# 08_-_USB.net
KiCad netlist of a schematic drawn in Altium Designer
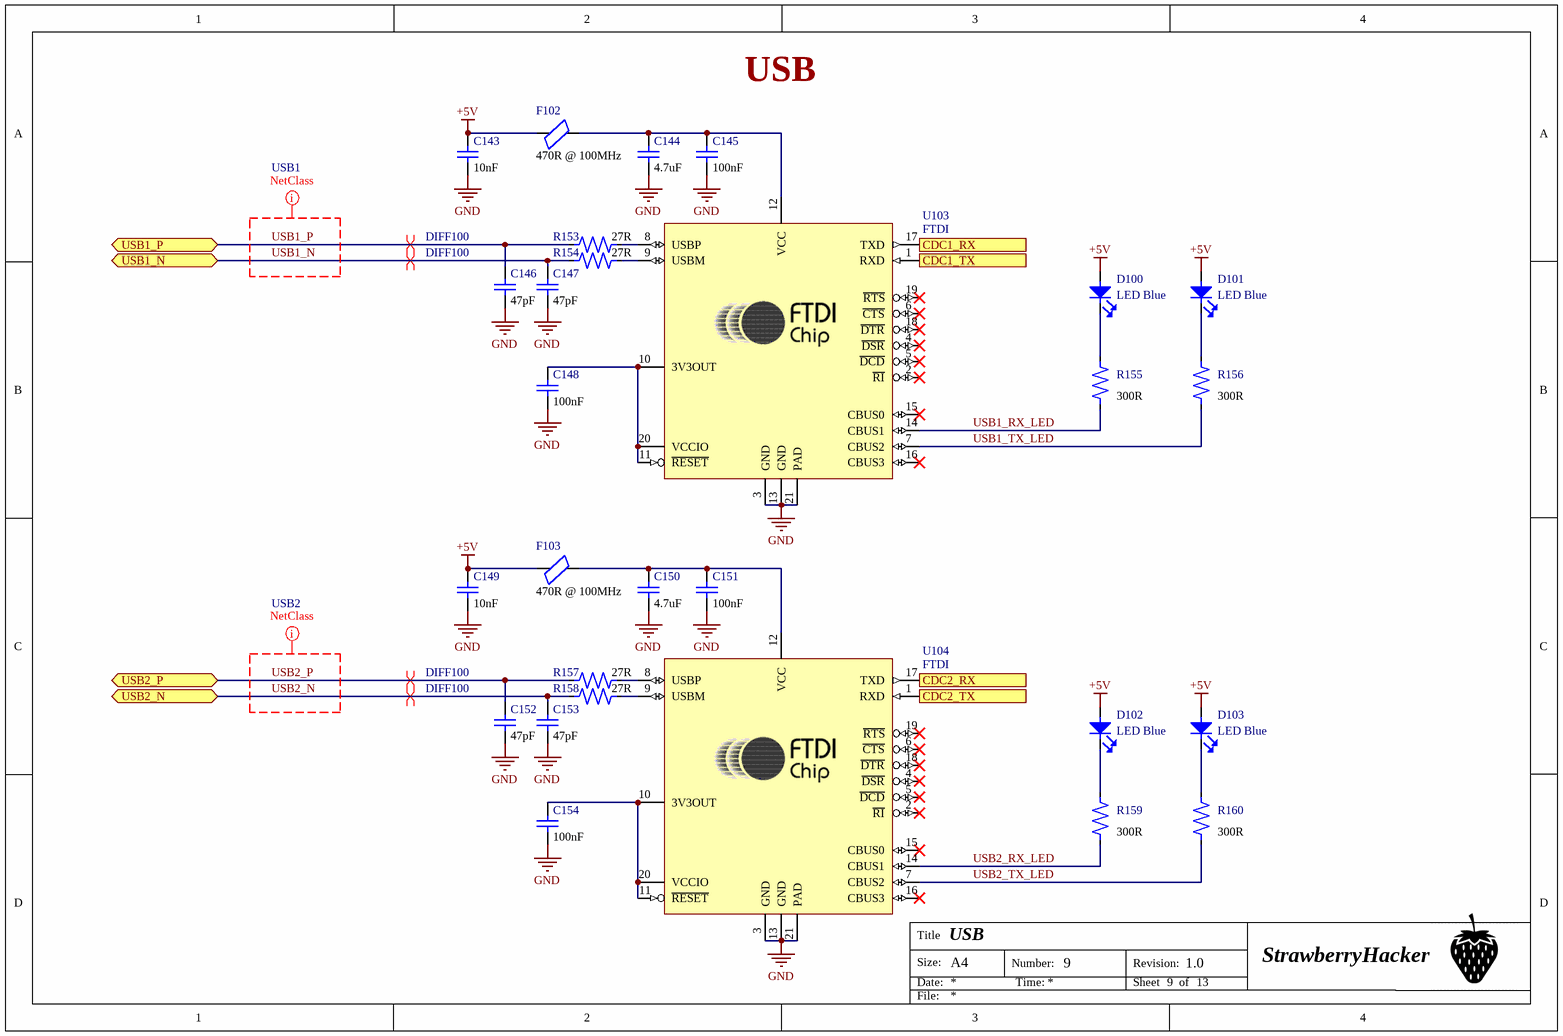
[diagram p0: [08] - USB.SchDoc]

(export (version "E")
  (design (tool "Eeschema 10.0.6"))
  (components
    (comp (ref "C143")
      (value "10nF")
      (footprint "C0402")
      (description "C0402")
      (fields (field (name "Comment") "04023C103KAT2A"))
      (libsource (lib "Passive components") (part "04023C103KAT2A"))
    )
    (comp (ref "C144")
      (value "4.7uF")
      (footprint "C0603")
      (description "C0603")
      (fields (field (name "Comment") "02016D104KAT2A"))
      (libsource (lib "Passive components") (part "02016D104KAT2A"))
    )
    (comp (ref "C145")
      (value "100nF")
      (footprint "C0402")
      (description "C0402")
      (fields (field (name "Comment") "04023C103KAT2A"))
      (libsource (lib "Passive components") (part "04023C103KAT2A"))
    )
    (comp (ref "C146")
      (value "47pF")
      (footprint "C0402")
      (description "C0402")
      (fields (field (name "Comment") "04023C103KAT2A"))
      (libsource (lib "Passive components") (part "04023C103KAT2A"))
    )
    (comp (ref "C147")
      (value "47pF")
      (footprint "C0402")
      (description "C0402")
      (fields (field (name "Comment") "04023C103KAT2A"))
      (libsource (lib "Passive components") (part "04023C103KAT2A"))
    )
    (comp (ref "C148")
      (value "100nF")
      (footprint "C0402")
      (description "C0402")
      (fields (field (name "Comment") "04023C103KAT2A"))
      (libsource (lib "Passive components") (part "04023C103KAT2A"))
    )
    (comp (ref "C149")
      (value "10nF")
      (footprint "C0402")
      (description "C0402")
      (fields (field (name "Comment") "04023C103KAT2A"))
      (libsource (lib "Passive components") (part "04023C103KAT2A"))
    )
    (comp (ref "C150")
      (value "4.7uF")
      (footprint "C0603")
      (description "C0603")
      (fields (field (name "Comment") "02016D104KAT2A"))
      (libsource (lib "Passive components") (part "02016D104KAT2A"))
    )
    (comp (ref "C151")
      (value "100nF")
      (footprint "C0402")
      (description "C0402")
      (fields (field (name "Comment") "04023C103KAT2A"))
      (libsource (lib "Passive components") (part "04023C103KAT2A"))
    )
    (comp (ref "C152")
      (value "47pF")
      (footprint "C0402")
      (description "C0402")
      (fields (field (name "Comment") "04023C103KAT2A"))
      (libsource (lib "Passive components") (part "04023C103KAT2A"))
    )
    (comp (ref "C153")
      (value "47pF")
      (footprint "C0402")
      (description "C0402")
      (fields (field (name "Comment") "04023C103KAT2A"))
      (libsource (lib "Passive components") (part "04023C103KAT2A"))
    )
    (comp (ref "C154")
      (value "100nF")
      (footprint "C0402")
      (description "C0402")
      (fields (field (name "Comment") "04023C103KAT2A"))
      (libsource (lib "Passive components") (part "04023C103KAT2A"))
    )
    (comp (ref "D100")
      (value "LED Blue")
      (footprint "L0603 BLUE")
      (description "LED 0603 Blue")
      (libsource (lib "Diodes") (part "HSMG-C199"))
    )
    (comp (ref "D101")
      (value "LED Blue")
      (footprint "L0603 BLUE")
      (description "LED 0603 Blue")
      (libsource (lib "Diodes") (part "HSMG-C199"))
    )
    (comp (ref "D102")
      (value "LED Blue")
      (footprint "L0603 BLUE")
      (description "LED 0603 Blue")
      (libsource (lib "Diodes") (part "HSMG-C199"))
    )
    (comp (ref "D103")
      (value "LED Blue")
      (footprint "L0603 BLUE")
      (description "LED 0603 Blue")
      (libsource (lib "Diodes") (part "HSMG-C199"))
    )
    (comp (ref "F102")
      (value "470R @ 100MHz")
      (footprint "Ferrite bead 0402")
      (description "Ferrite bead 0402")
      (fields (field (name "Comment") "BLM15AG102SN1D"))
      (libsource (lib "Passive components") (part "BLM15AG102SN1D"))
    )
    (comp (ref "F103")
      (value "470R @ 100MHz")
      (footprint "Ferrite bead 0402")
      (description "Ferrite bead 0402")
      (fields (field (name "Comment") "BLM15AG102SN1D"))
      (libsource (lib "Passive components") (part "BLM15AG102SN1D"))
    )
    (comp (ref "R153")
      (value "27R")
      (footprint "R0402")
      (description "R0402")
      (fields (field (name "Comment") "CRCW04020000Z0ED"))
      (libsource (lib "Passive components") (part "CRCW04020000Z0ED"))
    )
    (comp (ref "R154")
      (value "27R")
      (footprint "R0402")
      (description "R0402")
      (fields (field (name "Comment") "CRCW04020000Z0ED"))
      (libsource (lib "Passive components") (part "CRCW04020000Z0ED"))
    )
    (comp (ref "R155")
      (value "300R")
      (footprint "R0402")
      (description "R0402")
      (fields (field (name "Comment") "CRCW04020000Z0ED"))
      (libsource (lib "Passive components") (part "CRCW04020000Z0ED"))
    )
    (comp (ref "R156")
      (value "300R")
      (footprint "R0402")
      (description "R0402")
      (fields (field (name "Comment") "CRCW04020000Z0ED"))
      (libsource (lib "Passive components") (part "CRCW04020000Z0ED"))
    )
    (comp (ref "R157")
      (value "27R")
      (footprint "R0402")
      (description "R0402")
      (fields (field (name "Comment") "CRCW04020000Z0ED"))
      (libsource (lib "Passive components") (part "CRCW04020000Z0ED"))
    )
    (comp (ref "R158")
      (value "27R")
      (footprint "R0402")
      (description "R0402")
      (fields (field (name "Comment") "CRCW04020000Z0ED"))
      (libsource (lib "Passive components") (part "CRCW04020000Z0ED"))
    )
    (comp (ref "R159")
      (value "300R")
      (footprint "R0402")
      (description "R0402")
      (fields (field (name "Comment") "CRCW04020000Z0ED"))
      (libsource (lib "Passive components") (part "CRCW04020000Z0ED"))
    )
    (comp (ref "R160")
      (value "300R")
      (footprint "R0402")
      (description "R0402")
      (fields (field (name "Comment") "CRCW04020000Z0ED"))
      (libsource (lib "Passive components") (part "CRCW04020000Z0ED"))
    )
    (comp (ref "U103")
      (value "FTDI")
      (footprint "FT231XQ-R")
      (description "USB to RS-232 converter")
      (libsource (lib "IC") (part "FT231XQ-R"))
    )
    (comp (ref "U104")
      (value "FTDI")
      (footprint "FT231XQ-R")
      (description "USB to RS-232 converter")
      (libsource (lib "IC") (part "FT231XQ-R"))
    )
  )
  (nets
    (net (code "1") (name "+5V") (class "Default")
      (node (ref "C143") (pin "2") (pinfunction "2_2") (pintype "passive"))
      (node (ref "C149") (pin "2") (pinfunction "2_2") (pintype "passive"))
      (node (ref "D100") (pin "1") (pinfunction "1_1") (pintype "passive"))
      (node (ref "D101") (pin "1") (pinfunction "1_1") (pintype "passive"))
      (node (ref "D102") (pin "1") (pinfunction "1_1") (pintype "passive"))
      (node (ref "D103") (pin "1") (pinfunction "1_1") (pintype "passive"))
      (node (ref "F102") (pin "1") (pinfunction "1_1") (pintype "passive"))
      (node (ref "F103") (pin "1") (pinfunction "1_1") (pintype "passive"))
    )
    (net (code "2") (name "/CDC1_RX") (class "Default")
      (node (ref "U103") (pin "17") (pinfunction "TXD_17") (pintype "output"))
    )
    (net (code "3") (name "/CDC1_TX") (class "Default")
      (node (ref "U103") (pin "1") (pinfunction "RXD_1") (pintype "input"))
    )
    (net (code "4") (name "/CDC2_RX") (class "Default")
      (node (ref "U104") (pin "17") (pinfunction "TXD_17") (pintype "output"))
    )
    (net (code "5") (name "/CDC2_TX") (class "Default")
      (node (ref "U104") (pin "1") (pinfunction "RXD_1") (pintype "input"))
    )
    (net (code "6") (name "/USB1_N") (class "Default")
      (node (ref "C147") (pin "2") (pinfunction "2_2") (pintype "passive"))
      (node (ref "R154") (pin "1") (pinfunction "1_1") (pintype "passive"))
    )
    (net (code "7") (name "/USB1_P") (class "Default")
      (node (ref "C146") (pin "2") (pinfunction "2_2") (pintype "passive"))
      (node (ref "R153") (pin "1") (pinfunction "1_1") (pintype "passive"))
    )
    (net (code "8") (name "/USB1_RX_LED") (class "Default")
      (node (ref "R155") (pin "1") (pinfunction "1_1") (pintype "passive"))
      (node (ref "U103") (pin "14") (pinfunction "CBUS1_14") (pintype "bidirectional"))
    )
    (net (code "9") (name "/USB1_TX_LED") (class "Default")
      (node (ref "R156") (pin "1") (pinfunction "1_1") (pintype "passive"))
      (node (ref "U103") (pin "7") (pinfunction "CBUS2_7") (pintype "bidirectional"))
    )
    (net (code "10") (name "/USB2_N") (class "Default")
      (node (ref "C153") (pin "2") (pinfunction "2_2") (pintype "passive"))
      (node (ref "R158") (pin "1") (pinfunction "1_1") (pintype "passive"))
    )
    (net (code "11") (name "/USB2_P") (class "Default")
      (node (ref "C152") (pin "2") (pinfunction "2_2") (pintype "passive"))
      (node (ref "R157") (pin "1") (pinfunction "1_1") (pintype "passive"))
    )
    (net (code "12") (name "/USB2_RX_LED") (class "Default")
      (node (ref "R159") (pin "1") (pinfunction "1_1") (pintype "passive"))
      (node (ref "U104") (pin "14") (pinfunction "CBUS1_14") (pintype "bidirectional"))
    )
    (net (code "13") (name "/USB2_TX_LED") (class "Default")
      (node (ref "R160") (pin "1") (pinfunction "1_1") (pintype "passive"))
      (node (ref "U104") (pin "7") (pinfunction "CBUS2_7") (pintype "bidirectional"))
    )
    (net (code "14") (name "GND") (class "Default")
      (node (ref "C143") (pin "1") (pinfunction "1_1") (pintype "passive"))
      (node (ref "C144") (pin "1") (pinfunction "1_1") (pintype "passive"))
      (node (ref "C145") (pin "1") (pinfunction "1_1") (pintype "passive"))
      (node (ref "C146") (pin "1") (pinfunction "1_1") (pintype "passive"))
      (node (ref "C147") (pin "1") (pinfunction "1_1") (pintype "passive"))
      (node (ref "C148") (pin "1") (pinfunction "1_1") (pintype "passive"))
      (node (ref "C149") (pin "1") (pinfunction "1_1") (pintype "passive"))
      (node (ref "C150") (pin "1") (pinfunction "1_1") (pintype "passive"))
      (node (ref "C151") (pin "1") (pinfunction "1_1") (pintype "passive"))
      (node (ref "C152") (pin "1") (pinfunction "1_1") (pintype "passive"))
      (node (ref "C153") (pin "1") (pinfunction "1_1") (pintype "passive"))
      (node (ref "C154") (pin "1") (pinfunction "1_1") (pintype "passive"))
      (node (ref "U103") (pin "13") (pinfunction "GND_13") (pintype "power_in"))
      (node (ref "U103") (pin "21") (pinfunction "PAD_21") (pintype "power_in"))
      (node (ref "U103") (pin "3") (pinfunction "GND_3") (pintype "power_in"))
      (node (ref "U104") (pin "13") (pinfunction "GND_13") (pintype "power_in"))
      (node (ref "U104") (pin "21") (pinfunction "PAD_21") (pintype "power_in"))
      (node (ref "U104") (pin "3") (pinfunction "GND_3") (pintype "power_in"))
    )
    (net (code "15") (name "Net-(R153-3)") (class "Default")
      (node (ref "R153") (pin "2") (pinfunction "3_2") (pintype "passive"))
      (node (ref "U103") (pin "8") (pinfunction "USBP_8") (pintype "bidirectional"))
    )
    (net (code "16") (name "Net-(R154-3)") (class "Default")
      (node (ref "R154") (pin "2") (pinfunction "3_2") (pintype "passive"))
      (node (ref "U103") (pin "9") (pinfunction "USBM_9") (pintype "bidirectional"))
    )
    (net (code "17") (name "Net-(R155-3)") (class "Default")
      (node (ref "D100") (pin "2") (pinfunction "2_2") (pintype "passive"))
      (node (ref "R155") (pin "2") (pinfunction "3_2") (pintype "passive"))
    )
    (net (code "18") (name "Net-(R156-3)") (class "Default")
      (node (ref "D101") (pin "2") (pinfunction "2_2") (pintype "passive"))
      (node (ref "R156") (pin "2") (pinfunction "3_2") (pintype "passive"))
    )
    (net (code "19") (name "Net-(R157-3)") (class "Default")
      (node (ref "R157") (pin "2") (pinfunction "3_2") (pintype "passive"))
      (node (ref "U104") (pin "8") (pinfunction "USBP_8") (pintype "bidirectional"))
    )
    (net (code "20") (name "Net-(R158-3)") (class "Default")
      (node (ref "R158") (pin "2") (pinfunction "3_2") (pintype "passive"))
      (node (ref "U104") (pin "9") (pinfunction "USBM_9") (pintype "bidirectional"))
    )
    (net (code "21") (name "Net-(R159-3)") (class "Default")
      (node (ref "D102") (pin "2") (pinfunction "2_2") (pintype "passive"))
      (node (ref "R159") (pin "2") (pinfunction "3_2") (pintype "passive"))
    )
    (net (code "22") (name "Net-(R160-3)") (class "Default")
      (node (ref "D103") (pin "2") (pinfunction "2_2") (pintype "passive"))
      (node (ref "R160") (pin "2") (pinfunction "3_2") (pintype "passive"))
    )
    (net (code "23") (name "Net-(U103-3V3OUT)") (class "Default")
      (node (ref "C148") (pin "2") (pinfunction "2_2") (pintype "passive"))
      (node (ref "U103") (pin "10") (pinfunction "3V3OUT_10") (pintype "power_in"))
      (node (ref "U103") (pin "11") (pinfunction "~{RESET}_11") (pintype "input"))
      (node (ref "U103") (pin "20") (pinfunction "VCCIO_20") (pintype "power_in"))
    )
    (net (code "24") (name "Net-(U103-VCC)") (class "Default")
      (node (ref "C144") (pin "2") (pinfunction "2_2") (pintype "passive"))
      (node (ref "C145") (pin "2") (pinfunction "2_2") (pintype "passive"))
      (node (ref "F102") (pin "2") (pinfunction "2_2") (pintype "passive"))
      (node (ref "U103") (pin "12") (pinfunction "VCC_12") (pintype "power_in"))
    )
    (net (code "25") (name "Net-(U104-3V3OUT)") (class "Default")
      (node (ref "C154") (pin "2") (pinfunction "2_2") (pintype "passive"))
      (node (ref "U104") (pin "10") (pinfunction "3V3OUT_10") (pintype "power_in"))
      (node (ref "U104") (pin "11") (pinfunction "~{RESET}_11") (pintype "input"))
      (node (ref "U104") (pin "20") (pinfunction "VCCIO_20") (pintype "power_in"))
    )
    (net (code "26") (name "Net-(U104-VCC)") (class "Default")
      (node (ref "C150") (pin "2") (pinfunction "2_2") (pintype "passive"))
      (node (ref "C151") (pin "2") (pinfunction "2_2") (pintype "passive"))
      (node (ref "F103") (pin "2") (pinfunction "2_2") (pintype "passive"))
      (node (ref "U104") (pin "12") (pinfunction "VCC_12") (pintype "power_in"))
    )
    (net (code "27") (name "unconnected-(U103-CBUS0-Pad15)") (class "Default")
      (node (ref "U103") (pin "15") (pinfunction "CBUS0_15") (pintype "bidirectional+no_connect"))
    )
    (net (code "28") (name "unconnected-(U103-CBUS3-Pad16)") (class "Default")
      (node (ref "U103") (pin "16") (pinfunction "CBUS3_16") (pintype "bidirectional+no_connect"))
    )
    (net (code "29") (name "unconnected-(U103-~{CTS}-Pad6)") (class "Default")
      (node (ref "U103") (pin "6") (pinfunction "~{CTS}_6") (pintype "bidirectional+no_connect"))
    )
    (net (code "30") (name "unconnected-(U103-~{DCD}-Pad5)") (class "Default")
      (node (ref "U103") (pin "5") (pinfunction "~{DCD}_5") (pintype "bidirectional+no_connect"))
    )
    (net (code "31") (name "unconnected-(U103-~{DSR}-Pad4)") (class "Default")
      (node (ref "U103") (pin "4") (pinfunction "~{DSR}_4") (pintype "bidirectional+no_connect"))
    )
    (net (code "32") (name "unconnected-(U103-~{DTR}-Pad18)") (class "Default")
      (node (ref "U103") (pin "18") (pinfunction "~{DTR}_18") (pintype "bidirectional+no_connect"))
    )
    (net (code "33") (name "unconnected-(U103-~{RI}-Pad2)") (class "Default")
      (node (ref "U103") (pin "2") (pinfunction "~{RI}_2") (pintype "bidirectional+no_connect"))
    )
    (net (code "34") (name "unconnected-(U103-~{RTS}-Pad19)") (class "Default")
      (node (ref "U103") (pin "19") (pinfunction "~{RTS}_19") (pintype "bidirectional+no_connect"))
    )
    (net (code "35") (name "unconnected-(U104-CBUS0-Pad15)") (class "Default")
      (node (ref "U104") (pin "15") (pinfunction "CBUS0_15") (pintype "bidirectional+no_connect"))
    )
    (net (code "36") (name "unconnected-(U104-CBUS3-Pad16)") (class "Default")
      (node (ref "U104") (pin "16") (pinfunction "CBUS3_16") (pintype "bidirectional+no_connect"))
    )
    (net (code "37") (name "unconnected-(U104-~{CTS}-Pad6)") (class "Default")
      (node (ref "U104") (pin "6") (pinfunction "~{CTS}_6") (pintype "bidirectional+no_connect"))
    )
    (net (code "38") (name "unconnected-(U104-~{DCD}-Pad5)") (class "Default")
      (node (ref "U104") (pin "5") (pinfunction "~{DCD}_5") (pintype "bidirectional+no_connect"))
    )
    (net (code "39") (name "unconnected-(U104-~{DSR}-Pad4)") (class "Default")
      (node (ref "U104") (pin "4") (pinfunction "~{DSR}_4") (pintype "bidirectional+no_connect"))
    )
    (net (code "40") (name "unconnected-(U104-~{DTR}-Pad18)") (class "Default")
      (node (ref "U104") (pin "18") (pinfunction "~{DTR}_18") (pintype "bidirectional+no_connect"))
    )
    (net (code "41") (name "unconnected-(U104-~{RI}-Pad2)") (class "Default")
      (node (ref "U104") (pin "2") (pinfunction "~{RI}_2") (pintype "bidirectional+no_connect"))
    )
    (net (code "42") (name "unconnected-(U104-~{RTS}-Pad19)") (class "Default")
      (node (ref "U104") (pin "19") (pinfunction "~{RTS}_19") (pintype "bidirectional+no_connect"))
    )
  )
)
